# SECDONGL_001.net
KiCad netlist of a schematic drawn in EAGLE
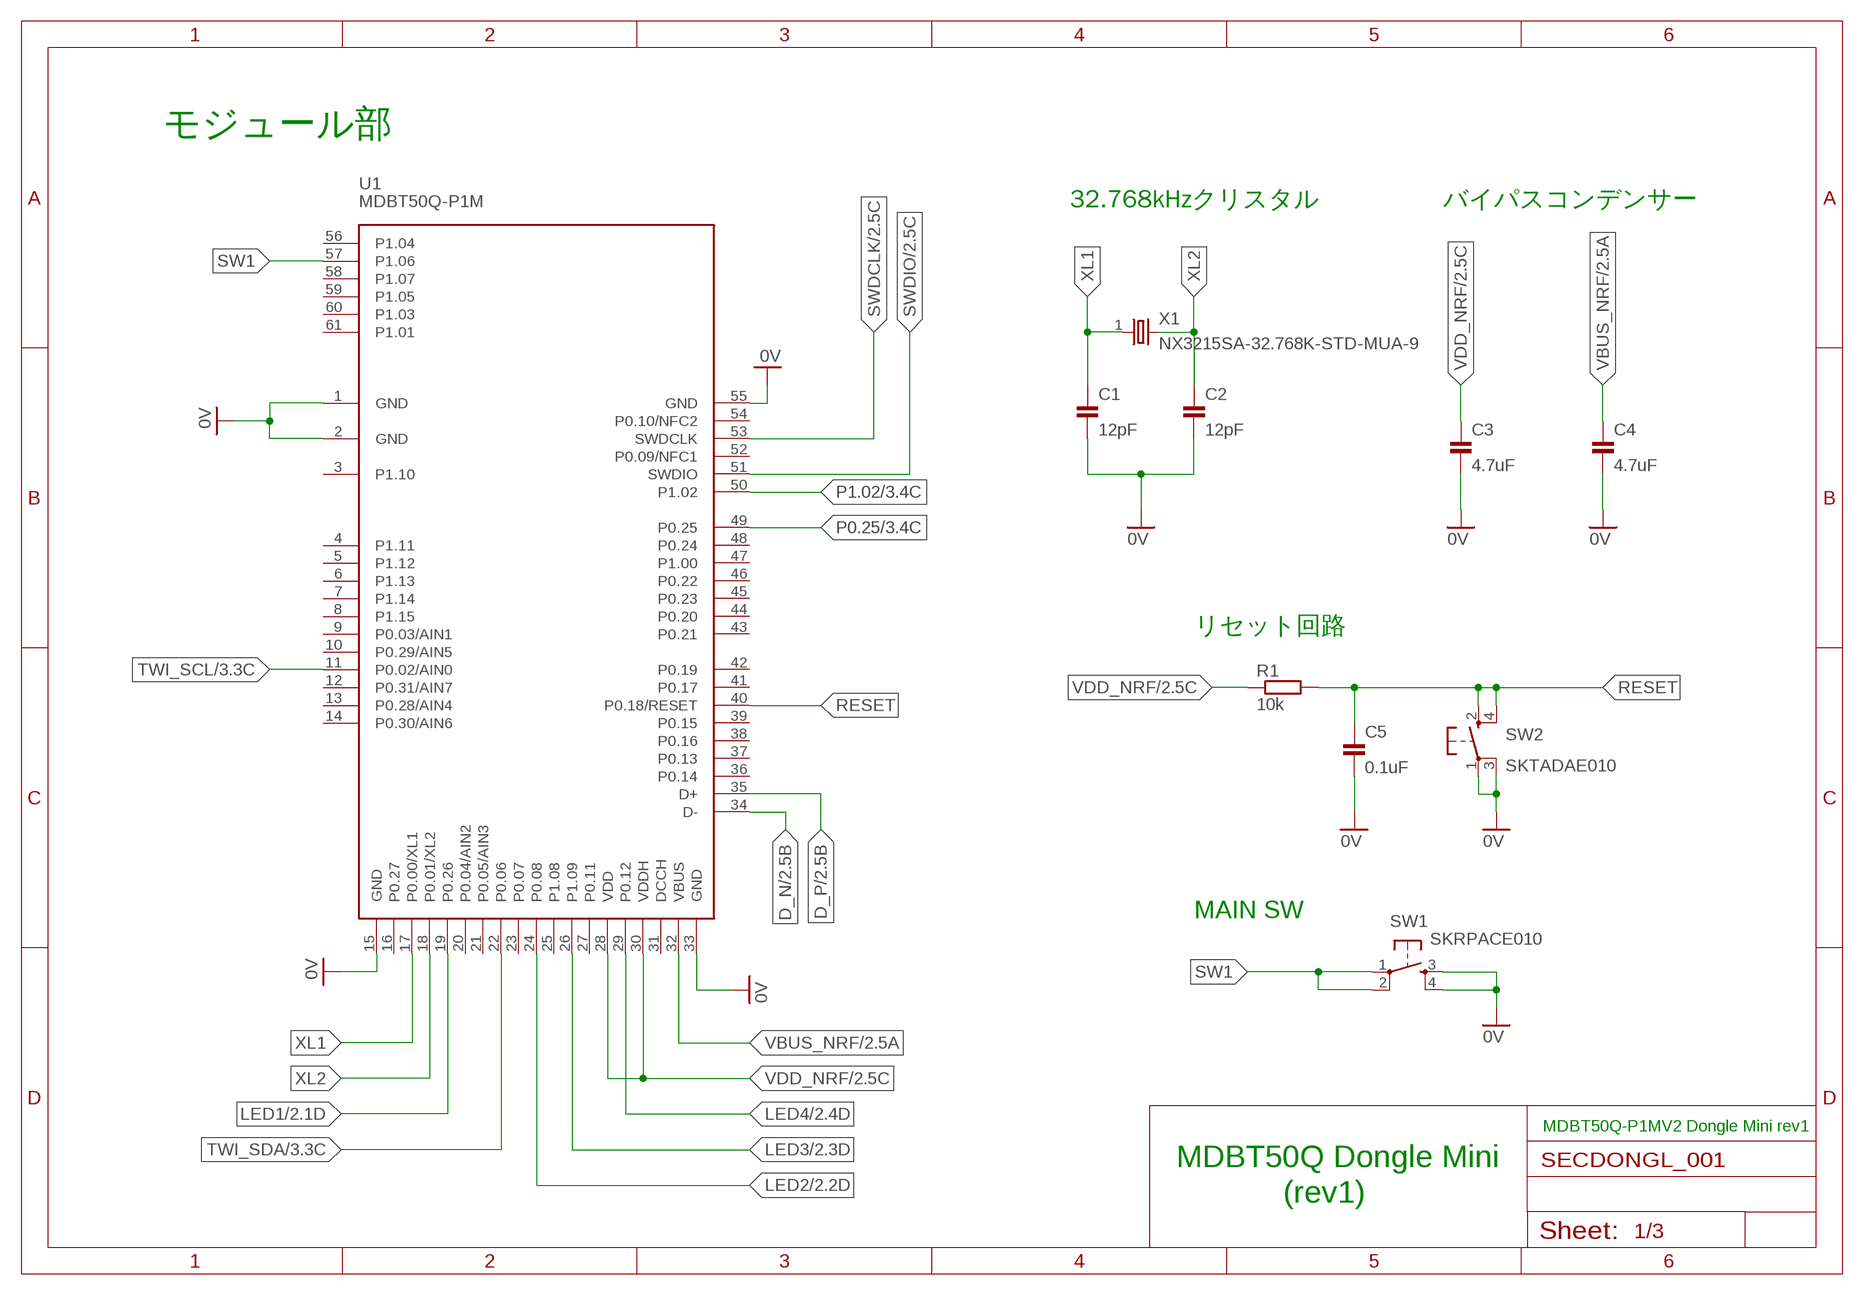
[diagram p0: schematic, sheet 1]
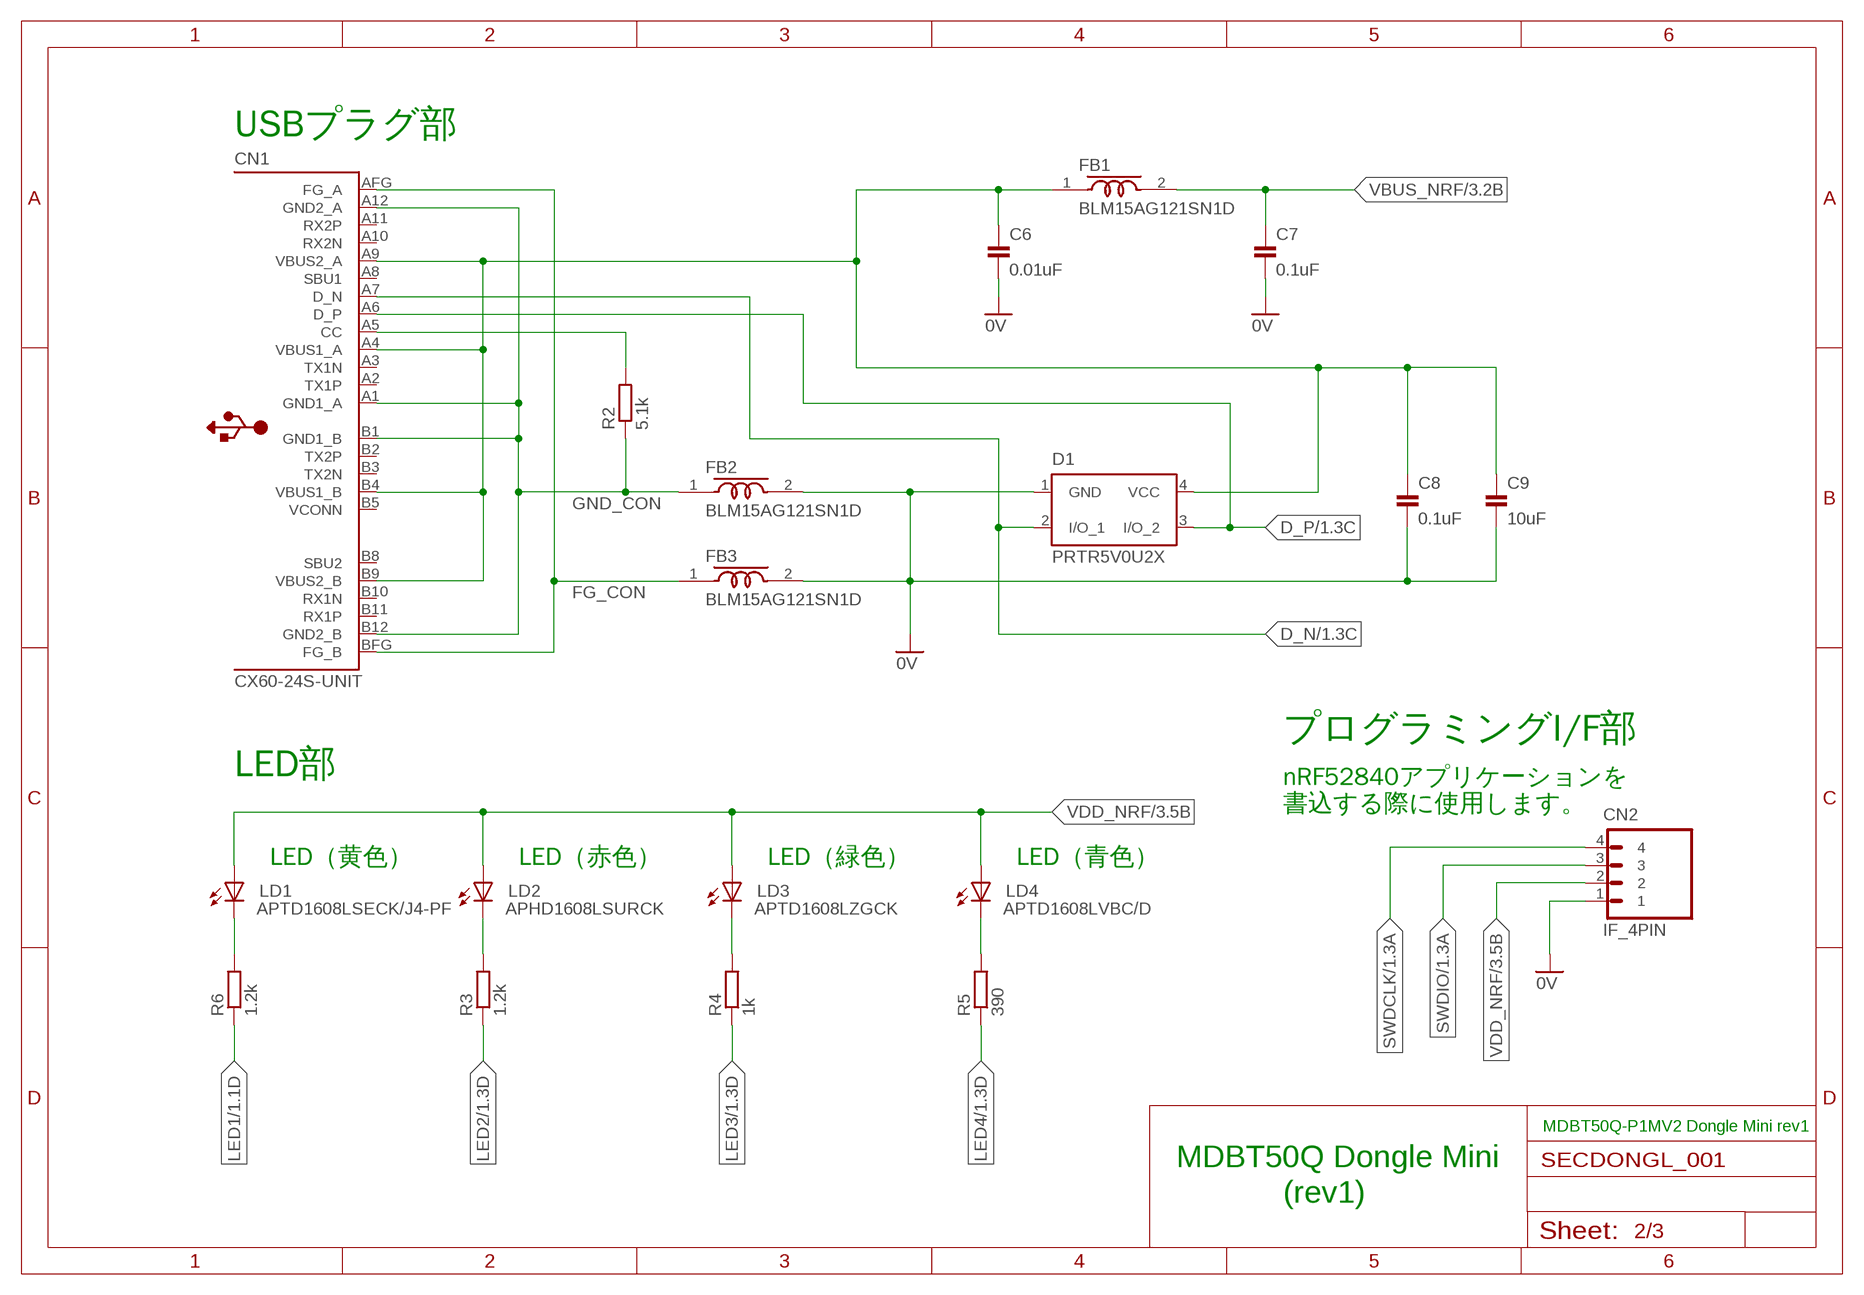
[diagram p1: schematic, sheet 2]
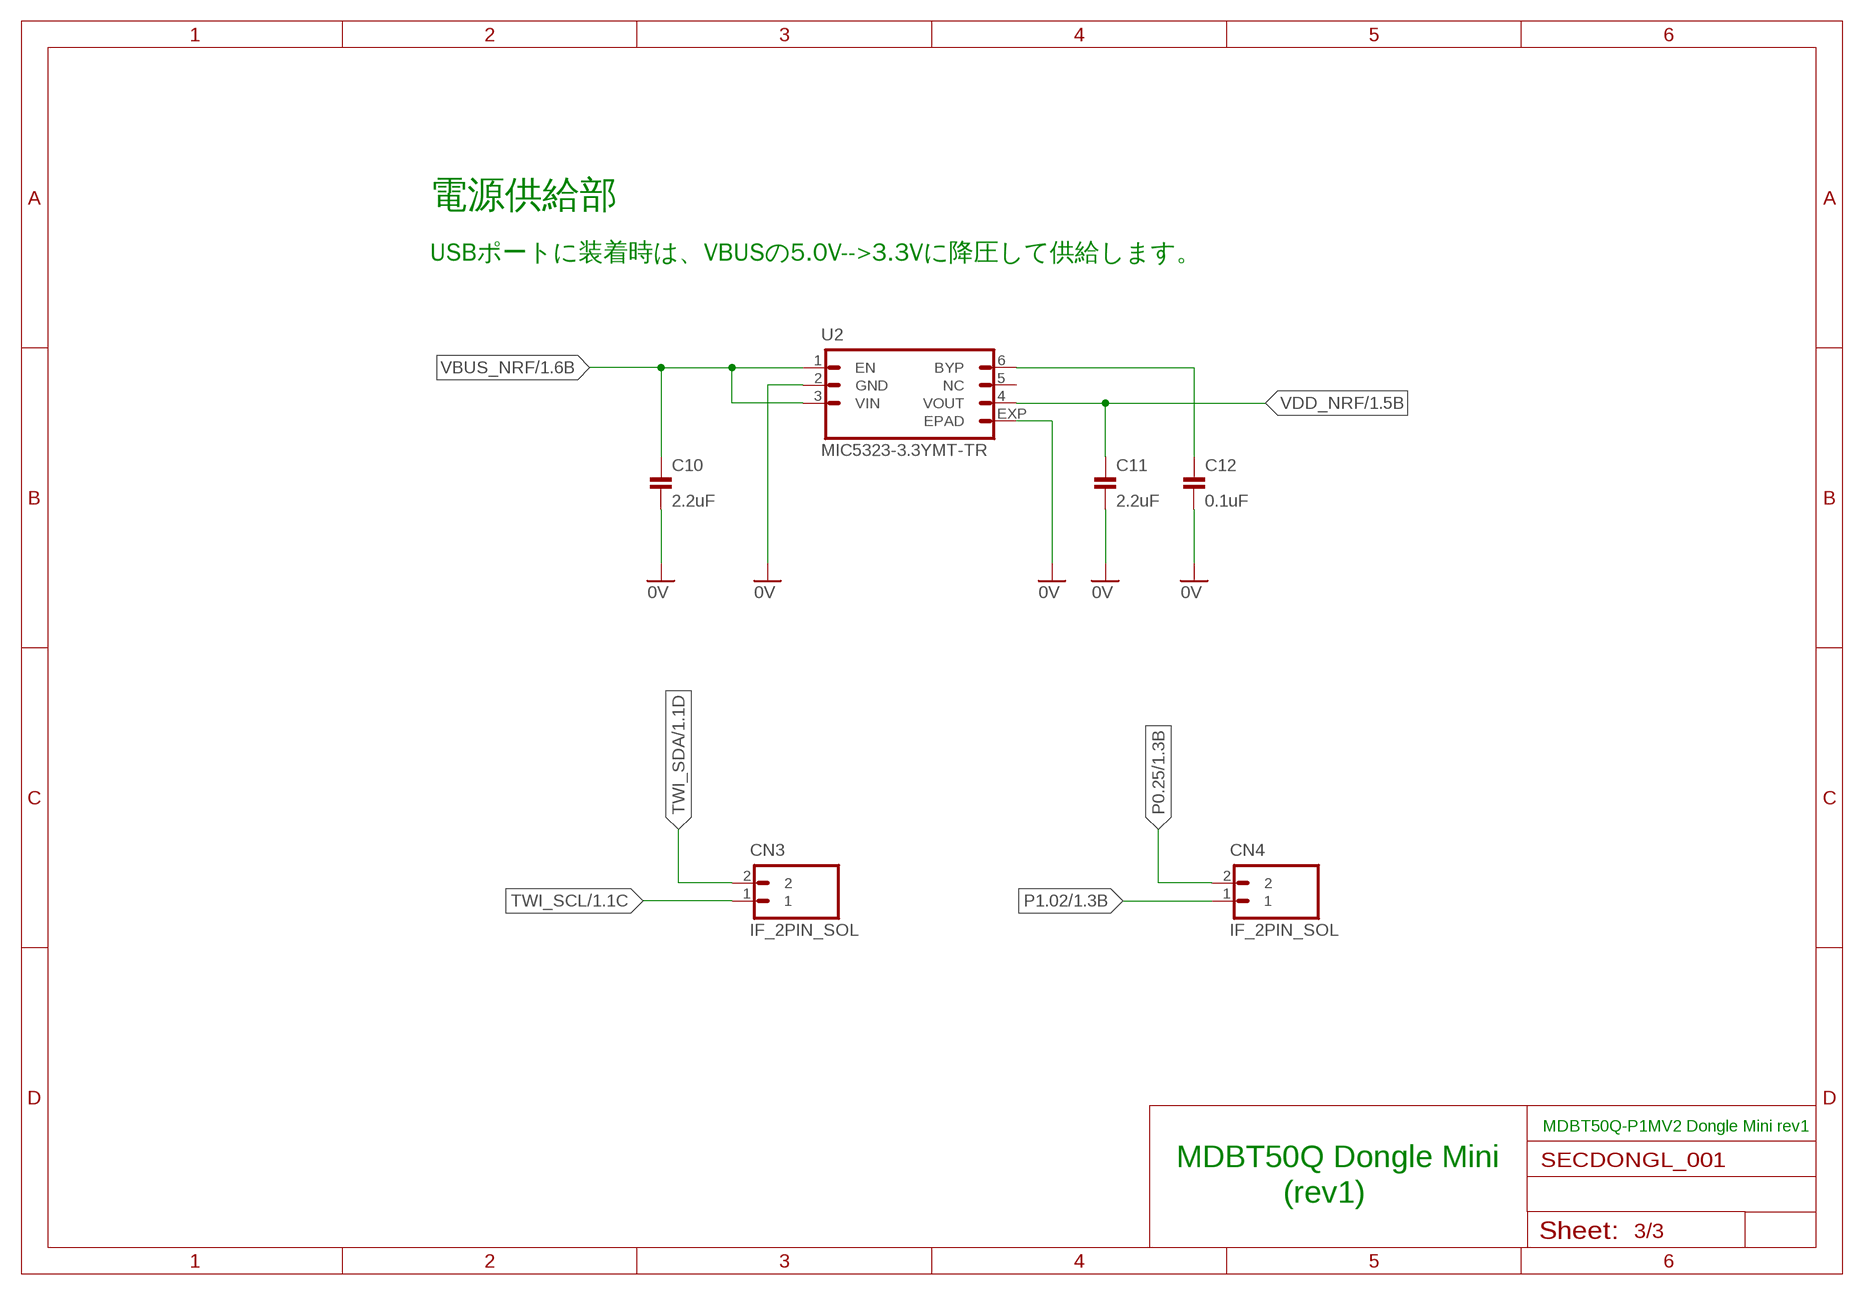
[diagram p2: schematic, sheet 3]

(export (version "E")
  (design (tool "Eeschema 10.0.6"))
  (components
    (comp (ref "C6")
      (value "0.01uF")
      (footprint "eagle-import:C0402K")
      (libsource (lib "eagle-import") (part "CAP_0402K"))
    )
    (comp (ref "C7")
      (value "0.1uF")
      (footprint "eagle-import:C0402K")
      (libsource (lib "eagle-import") (part "CAP_0402K"))
    )
    (comp (ref "C8")
      (value "0.1uF")
      (footprint "eagle-import:C0402K")
      (libsource (lib "eagle-import") (part "CAP_0402K"))
    )
    (comp (ref "C9")
      (value "10uF")
      (footprint "eagle-import:C0603K")
      (libsource (lib "eagle-import") (part "CAP_0603"))
    )
    (comp (ref "CN1")
      (value "CX60-24S-UNIT")
      (footprint "eagle-import:CX60-24S-UNIT")
      (libsource (lib "eagle-import") (part "CX60-24S-UNIT"))
    )
    (comp (ref "CN2")
      (value "IF_4PIN")
      (footprint "eagle-import:HEADER_4PIN")
      (libsource (lib "eagle-import") (part "IF_4PIN"))
    )
    (comp (ref "D1")
      (value "PRTR5V0U2X")
      (footprint "eagle-import:SOT143B")
      (libsource (lib "eagle-import") (part "PRTR5V0U2X"))
    )
    (comp (ref "FB1")
      (value "BLM15AG121SN1D")
      (footprint "eagle-import:C0402K")
      (libsource (lib "eagle-import") (part "BLM15AG121SN1D"))
    )
    (comp (ref "FB2")
      (value "BLM15AG121SN1D")
      (footprint "eagle-import:C0402K")
      (libsource (lib "eagle-import") (part "BLM15AG121SN1D"))
    )
    (comp (ref "FB3")
      (value "BLM15AG121SN1D")
      (footprint "eagle-import:C0402K")
      (libsource (lib "eagle-import") (part "BLM15AG121SN1D"))
    )
    (comp (ref "LD1")
      (value "APTD1608LSECK/J4-PF")
      (footprint "eagle-import:APTD1608")
      (libsource (lib "eagle-import") (part "APTD1608LSECK/J4-PF"))
    )
    (comp (ref "LD2")
      (value "APHD1608LSURCK")
      (footprint "eagle-import:APTD1608")
      (libsource (lib "eagle-import") (part "APHD1608LSURCK"))
    )
    (comp (ref "LD3")
      (value "APTD1608LZGCK")
      (footprint "eagle-import:APTD1608")
      (libsource (lib "eagle-import") (part "APTD1608LZGCK"))
    )
    (comp (ref "LD4")
      (value "APTD1608LVBC/D")
      (footprint "eagle-import:APTD1608")
      (libsource (lib "eagle-import") (part "APTD1608LVBC/D"))
    )
    (comp (ref "R2")
      (value "5.1k")
      (footprint "eagle-import:R0402")
      (libsource (lib "eagle-import") (part "RESISTOR_0402"))
    )
    (comp (ref "R3")
      (value "1.2k")
      (footprint "eagle-import:R0402")
      (libsource (lib "eagle-import") (part "RESISTOR_0402"))
    )
    (comp (ref "R4")
      (value "1k")
      (footprint "eagle-import:R0402")
      (libsource (lib "eagle-import") (part "RESISTOR_0402"))
    )
    (comp (ref "R5")
      (value "390")
      (footprint "eagle-import:R0402")
      (libsource (lib "eagle-import") (part "RESISTOR_0402"))
    )
    (comp (ref "R6")
      (value "1.2k")
      (footprint "eagle-import:R0402")
      (libsource (lib "eagle-import") (part "RESISTOR_0402"))
    )
    (comp (ref "C1")
      (value "12pF")
      (footprint "eagle-import:C0603K")
      (libsource (lib "eagle-import") (part "CAP_0603"))
    )
    (comp (ref "C2")
      (value "12pF")
      (footprint "eagle-import:C0603K")
      (libsource (lib "eagle-import") (part "CAP_0603"))
    )
    (comp (ref "C3")
      (value "4.7uF")
      (footprint "eagle-import:C0603K")
      (libsource (lib "eagle-import") (part "CAP_0603"))
    )
    (comp (ref "C4")
      (value "4.7uF")
      (footprint "eagle-import:C0603K")
      (libsource (lib "eagle-import") (part "CAP_0603"))
    )
    (comp (ref "C5")
      (value "0.1uF")
      (footprint "eagle-import:C0402K")
      (libsource (lib "eagle-import") (part "CAP_0402K"))
    )
    (comp (ref "R1")
      (value "10k")
      (footprint "eagle-import:R0402")
      (libsource (lib "eagle-import") (part "RESISTOR_0402"))
    )
    (comp (ref "SW1")
      (value "SKRPACE010")
      (footprint "eagle-import:SKRPACE010")
      (libsource (lib "eagle-import") (part "SKRPACE010"))
    )
    (comp (ref "SW2")
      (value "SKTADAE010")
      (footprint "eagle-import:SKTADAE010")
      (libsource (lib "eagle-import") (part "SKTADAE010"))
    )
    (comp (ref "U1")
      (value "MDBT50Q-P1M")
      (footprint "eagle-import:MDBT50Q-P1M")
      (libsource (lib "eagle-import") (part "MDBT50Q-P1M"))
    )
    (comp (ref "X1")
      (value "NX3215SA-32.768K-STD-MUA-9")
      (footprint "eagle-import:NX3215")
      (libsource (lib "eagle-import") (part "NX3215SA-32.768K-STD-MUA-9"))
    )
    (comp (ref "C10")
      (value "2.2uF")
      (footprint "eagle-import:C0603K")
      (libsource (lib "eagle-import") (part "CAP_0603"))
    )
    (comp (ref "C11")
      (value "2.2uF")
      (footprint "eagle-import:C0603K")
      (libsource (lib "eagle-import") (part "CAP_0603"))
    )
    (comp (ref "C12")
      (value "0.1uF")
      (footprint "eagle-import:C0402K")
      (libsource (lib "eagle-import") (part "CAP_0402K"))
    )
    (comp (ref "CN3")
      (value "IF_2PIN_SOL")
      (footprint "eagle-import:SOLPAD_2PIN")
      (libsource (lib "eagle-import") (part "IF_2PIN_SOL"))
    )
    (comp (ref "CN4")
      (value "IF_2PIN_SOL")
      (footprint "eagle-import:SOLPAD_2PIN")
      (libsource (lib "eagle-import") (part "IF_2PIN_SOL"))
    )
    (comp (ref "U2")
      (value "MIC5323-3.3YMT-TR")
      (footprint "eagle-import:6-VDFN(2X2)")
      (libsource (lib "eagle-import") (part "MIC5323-3.3YMT-TR"))
    )
  )
  (nets
    (net (code "1") (name "0V") (class "Default")
      (node (ref "C1") (pin "2") (pinfunction "2_2") (pintype "passive"))
      (node (ref "C10") (pin "2") (pinfunction "2_2") (pintype "passive"))
      (node (ref "C11") (pin "2") (pinfunction "2_2") (pintype "passive"))
      (node (ref "C12") (pin "2") (pinfunction "2_2") (pintype "passive"))
      (node (ref "C2") (pin "2") (pinfunction "2_2") (pintype "passive"))
      (node (ref "C3") (pin "2") (pinfunction "2_2") (pintype "passive"))
      (node (ref "C4") (pin "2") (pinfunction "2_2") (pintype "passive"))
      (node (ref "C5") (pin "2") (pinfunction "2_2") (pintype "passive"))
      (node (ref "C6") (pin "2") (pinfunction "2_2") (pintype "passive"))
      (node (ref "C7") (pin "2") (pinfunction "2_2") (pintype "passive"))
      (node (ref "C8") (pin "2") (pinfunction "2_2") (pintype "passive"))
      (node (ref "C9") (pin "2") (pinfunction "2_2") (pintype "passive"))
      (node (ref "CN2") (pin "1") (pinfunction "1_1") (pintype "passive"))
      (node (ref "D1") (pin "1") (pinfunction "GND_1") (pintype "passive"))
      (node (ref "FB2") (pin "2") (pinfunction "2_2") (pintype "passive"))
      (node (ref "FB3") (pin "2") (pinfunction "2_2") (pintype "passive"))
      (node (ref "SW1") (pin "3") (pinfunction "S_3") (pintype "passive"))
      (node (ref "SW1") (pin "4") (pinfunction "S1_4") (pintype "passive"))
      (node (ref "SW2") (pin "1") (pinfunction "P_1") (pintype "passive"))
      (node (ref "SW2") (pin "3") (pinfunction "P1_3") (pintype "passive"))
      (node (ref "U1") (pin "1") (pinfunction "GND_1") (pintype "bidirectional"))
      (node (ref "U1") (pin "15") (pinfunction "GND_15") (pintype "bidirectional"))
      (node (ref "U1") (pin "2") (pinfunction "GND_2") (pintype "bidirectional"))
      (node (ref "U1") (pin "33") (pinfunction "GND_33") (pintype "bidirectional"))
      (node (ref "U1") (pin "55") (pinfunction "GND_55") (pintype "bidirectional"))
      (node (ref "U2") (pin "2") (pinfunction "GND_2") (pintype "passive"))
      (node (ref "U2") (pin "EXP") (pinfunction "EPAD_EXP") (pintype "passive"))
    )
    (net (code "2") (name "D_N") (class "Default")
      (node (ref "CN1") (pin "A7") (pinfunction "D_N_A7") (pintype "bidirectional"))
      (node (ref "D1") (pin "2") (pinfunction "I/O_1_2") (pintype "bidirectional"))
      (node (ref "U1") (pin "34") (pinfunction "D-_34") (pintype "bidirectional"))
    )
    (net (code "3") (name "D_P") (class "Default")
      (node (ref "CN1") (pin "A6") (pinfunction "D_P_A6") (pintype "bidirectional"))
      (node (ref "D1") (pin "3") (pinfunction "I/O_2_3") (pintype "bidirectional"))
      (node (ref "U1") (pin "35") (pinfunction "D+_35") (pintype "bidirectional"))
    )
    (net (code "4") (name "FG_CON") (class "Default")
      (node (ref "CN1") (pin "AFG") (pinfunction "FG_A_AFG") (pintype "passive"))
      (node (ref "CN1") (pin "BFG") (pinfunction "FG_B_BFG") (pintype "passive"))
      (node (ref "FB3") (pin "1") (pinfunction "1_1") (pintype "passive"))
    )
    (net (code "5") (name "GND_CON") (class "Default")
      (node (ref "CN1") (pin "A1") (pinfunction "GND1_A_A1") (pintype "passive"))
      (node (ref "CN1") (pin "A12") (pinfunction "GND2_A_A12") (pintype "bidirectional"))
      (node (ref "CN1") (pin "B1") (pinfunction "GND1_B_B1") (pintype "passive"))
      (node (ref "CN1") (pin "B12") (pinfunction "GND2_B_B12") (pintype "passive"))
      (node (ref "FB2") (pin "1") (pinfunction "1_1") (pintype "passive"))
      (node (ref "R2") (pin "1") (pinfunction "1_1") (pintype "passive"))
    )
    (net (code "6") (name "LED1") (class "Default")
      (node (ref "R6") (pin "1") (pinfunction "1_1") (pintype "passive"))
      (node (ref "U1") (pin "19") (pinfunction "P0.26_19") (pintype "bidirectional"))
    )
    (net (code "7") (name "LED2") (class "Default")
      (node (ref "R3") (pin "1") (pinfunction "1_1") (pintype "passive"))
      (node (ref "U1") (pin "24") (pinfunction "P0.08_24") (pintype "bidirectional"))
    )
    (net (code "8") (name "LED3") (class "Default")
      (node (ref "R4") (pin "1") (pinfunction "1_1") (pintype "passive"))
      (node (ref "U1") (pin "26") (pinfunction "P1.09_26") (pintype "bidirectional"))
    )
    (net (code "9") (name "LED4") (class "Default")
      (node (ref "R5") (pin "1") (pinfunction "1_1") (pintype "passive"))
      (node (ref "U1") (pin "29") (pinfunction "P0.12_29") (pintype "bidirectional"))
    )
    (net (code "10") (name "Net-(CN1-CC)") (class "Default")
      (node (ref "CN1") (pin "A5") (pinfunction "CC_A5") (pintype "passive"))
      (node (ref "R2") (pin "2") (pinfunction "2_2") (pintype "passive"))
    )
    (net (code "11") (name "Net-(CN1-VBUS1_A)") (class "Default")
      (node (ref "C6") (pin "1") (pinfunction "1_1") (pintype "passive"))
      (node (ref "C8") (pin "1") (pinfunction "1_1") (pintype "passive"))
      (node (ref "C9") (pin "1") (pinfunction "1_1") (pintype "passive"))
      (node (ref "CN1") (pin "A4") (pinfunction "VBUS1_A_A4") (pintype "passive"))
      (node (ref "CN1") (pin "A9") (pinfunction "VBUS2_A_A9") (pintype "passive"))
      (node (ref "CN1") (pin "B4") (pinfunction "VBUS1_B_B4") (pintype "passive"))
      (node (ref "CN1") (pin "B9") (pinfunction "VBUS2_B_B9") (pintype "passive"))
      (node (ref "D1") (pin "4") (pinfunction "VCC_4") (pintype "passive"))
      (node (ref "FB1") (pin "1") (pinfunction "1_1") (pintype "passive"))
    )
    (net (code "12") (name "Net-(LD1-PadC)") (class "Default")
      (node (ref "LD1") (pin "C") (pinfunction "C_C") (pintype "passive"))
      (node (ref "R6") (pin "2") (pinfunction "2_2") (pintype "passive"))
    )
    (net (code "13") (name "Net-(LD2-PadC)") (class "Default")
      (node (ref "LD2") (pin "C") (pinfunction "C_C") (pintype "passive"))
      (node (ref "R3") (pin "2") (pinfunction "2_2") (pintype "passive"))
    )
    (net (code "14") (name "Net-(LD3-PadC)") (class "Default")
      (node (ref "LD3") (pin "C") (pinfunction "C_C") (pintype "passive"))
      (node (ref "R4") (pin "2") (pinfunction "2_2") (pintype "passive"))
    )
    (net (code "15") (name "Net-(LD4-PadC)") (class "Default")
      (node (ref "LD4") (pin "C") (pinfunction "C_C") (pintype "passive"))
      (node (ref "R5") (pin "2") (pinfunction "2_2") (pintype "passive"))
    )
    (net (code "16") (name "Net-(U2-BYP)") (class "Default")
      (node (ref "C12") (pin "1") (pinfunction "1_1") (pintype "passive"))
      (node (ref "U2") (pin "6") (pinfunction "BYP_6") (pintype "passive"))
    )
    (net (code "17") (name "P0.25") (class "Default")
      (node (ref "CN4") (pin "2") (pinfunction "2_2") (pintype "passive"))
      (node (ref "U1") (pin "49") (pinfunction "P0.25_49") (pintype "bidirectional"))
    )
    (net (code "18") (name "P1.02") (class "Default")
      (node (ref "CN4") (pin "1") (pinfunction "1_1") (pintype "passive"))
      (node (ref "U1") (pin "50") (pinfunction "P1.02_50") (pintype "bidirectional"))
    )
    (net (code "19") (name "RESET") (class "Default")
      (node (ref "C5") (pin "1") (pinfunction "1_1") (pintype "passive"))
      (node (ref "R1") (pin "2") (pinfunction "2_2") (pintype "passive"))
      (node (ref "SW2") (pin "2") (pinfunction "S_2") (pintype "passive"))
      (node (ref "SW2") (pin "4") (pinfunction "S1_4") (pintype "passive"))
      (node (ref "U1") (pin "40") (pinfunction "P0.18/RESET_40") (pintype "bidirectional"))
    )
    (net (code "20") (name "SW1") (class "Default")
      (node (ref "SW1") (pin "1") (pinfunction "P_1") (pintype "passive"))
      (node (ref "SW1") (pin "2") (pinfunction "P1_2") (pintype "passive"))
      (node (ref "U1") (pin "57") (pinfunction "P1.06_57") (pintype "bidirectional"))
    )
    (net (code "21") (name "SWDCLK") (class "Default")
      (node (ref "CN2") (pin "4") (pinfunction "4_4") (pintype "passive"))
      (node (ref "U1") (pin "53") (pinfunction "SWDCLK_53") (pintype "bidirectional"))
    )
    (net (code "22") (name "SWDIO") (class "Default")
      (node (ref "CN2") (pin "3") (pinfunction "3_3") (pintype "passive"))
      (node (ref "U1") (pin "51") (pinfunction "SWDIO_51") (pintype "bidirectional"))
    )
    (net (code "23") (name "TWI_SCL") (class "Default")
      (node (ref "CN3") (pin "1") (pinfunction "1_1") (pintype "passive"))
      (node (ref "U1") (pin "11") (pinfunction "P0.02/AIN0_11") (pintype "bidirectional"))
    )
    (net (code "24") (name "TWI_SDA") (class "Default")
      (node (ref "CN3") (pin "2") (pinfunction "2_2") (pintype "passive"))
      (node (ref "U1") (pin "22") (pinfunction "P0.06_22") (pintype "bidirectional"))
    )
    (net (code "25") (name "VBUS_NRF") (class "Default")
      (node (ref "C10") (pin "1") (pinfunction "1_1") (pintype "passive"))
      (node (ref "C4") (pin "1") (pinfunction "1_1") (pintype "passive"))
      (node (ref "C7") (pin "1") (pinfunction "1_1") (pintype "passive"))
      (node (ref "FB1") (pin "2") (pinfunction "2_2") (pintype "passive"))
      (node (ref "U1") (pin "32") (pinfunction "VBUS_32") (pintype "bidirectional"))
      (node (ref "U2") (pin "1") (pinfunction "EN_1") (pintype "bidirectional"))
      (node (ref "U2") (pin "3") (pinfunction "VIN_3") (pintype "passive"))
    )
    (net (code "26") (name "VDD_NRF") (class "Default")
      (node (ref "C11") (pin "1") (pinfunction "1_1") (pintype "passive"))
      (node (ref "C3") (pin "1") (pinfunction "1_1") (pintype "passive"))
      (node (ref "CN2") (pin "2") (pinfunction "2_2") (pintype "passive"))
      (node (ref "LD1") (pin "A") (pinfunction "A_A") (pintype "passive"))
      (node (ref "LD2") (pin "A") (pinfunction "A_A") (pintype "passive"))
      (node (ref "LD3") (pin "A") (pinfunction "A_A") (pintype "passive"))
      (node (ref "LD4") (pin "A") (pinfunction "A_A") (pintype "passive"))
      (node (ref "R1") (pin "1") (pinfunction "1_1") (pintype "passive"))
      (node (ref "U1") (pin "28") (pinfunction "VDD_28") (pintype "bidirectional"))
      (node (ref "U1") (pin "30") (pinfunction "VDDH_30") (pintype "bidirectional"))
      (node (ref "U2") (pin "4") (pinfunction "VOUT_4") (pintype "passive"))
    )
    (net (code "27") (name "XL1") (class "Default")
      (node (ref "C1") (pin "1") (pinfunction "1_1") (pintype "passive"))
      (node (ref "U1") (pin "17") (pinfunction "P0.00/XL1_17") (pintype "bidirectional"))
      (node (ref "X1") (pin "1") (pinfunction "1_1") (pintype "passive"))
    )
    (net (code "28") (name "XL2") (class "Default")
      (node (ref "C2") (pin "1") (pinfunction "1_1") (pintype "passive"))
      (node (ref "U1") (pin "18") (pinfunction "P0.01/XL2_18") (pintype "bidirectional"))
      (node (ref "X1") (pin "2") (pinfunction "2_2") (pintype "passive"))
    )
    (net (code "29") (name "unconnected-(CN1-RX1N-PadB10)") (class "Default")
      (node (ref "CN1") (pin "B10") (pinfunction "RX1N_B10") (pintype "bidirectional"))
    )
    (net (code "30") (name "unconnected-(CN1-RX1P-PadB11)") (class "Default")
      (node (ref "CN1") (pin "B11") (pinfunction "RX1P_B11") (pintype "bidirectional"))
    )
    (net (code "31") (name "unconnected-(CN1-RX2N-PadA10)") (class "Default")
      (node (ref "CN1") (pin "A10") (pinfunction "RX2N_A10") (pintype "passive"))
    )
    (net (code "32") (name "unconnected-(CN1-RX2P-PadA11)") (class "Default")
      (node (ref "CN1") (pin "A11") (pinfunction "RX2P_A11") (pintype "bidirectional"))
    )
    (net (code "33") (name "unconnected-(CN1-SBU1-PadA8)") (class "Default")
      (node (ref "CN1") (pin "A8") (pinfunction "SBU1_A8") (pintype "passive"))
    )
    (net (code "34") (name "unconnected-(CN1-SBU2-PadB8)") (class "Default")
      (node (ref "CN1") (pin "B8") (pinfunction "SBU2_B8") (pintype "passive"))
    )
    (net (code "35") (name "unconnected-(CN1-TX1N-PadA3)") (class "Default")
      (node (ref "CN1") (pin "A3") (pinfunction "TX1N_A3") (pintype "bidirectional"))
    )
    (net (code "36") (name "unconnected-(CN1-TX1P-PadA2)") (class "Default")
      (node (ref "CN1") (pin "A2") (pinfunction "TX1P_A2") (pintype "bidirectional"))
    )
    (net (code "37") (name "unconnected-(CN1-TX2N-PadB3)") (class "Default")
      (node (ref "CN1") (pin "B3") (pinfunction "TX2N_B3") (pintype "bidirectional"))
    )
    (net (code "38") (name "unconnected-(CN1-TX2P-PadB2)") (class "Default")
      (node (ref "CN1") (pin "B2") (pinfunction "TX2P_B2") (pintype "bidirectional"))
    )
    (net (code "39") (name "unconnected-(CN1-VCONN-PadB5)") (class "Default")
      (node (ref "CN1") (pin "B5") (pinfunction "VCONN_B5") (pintype "passive"))
    )
    (net (code "40") (name "unconnected-(U1-DCCH-Pad31)") (class "Default")
      (node (ref "U1") (pin "31") (pinfunction "DCCH_31") (pintype "bidirectional"))
    )
    (net (code "41") (name "unconnected-(U1-P0.03{slash}AIN1-Pad9)") (class "Default")
      (node (ref "U1") (pin "9") (pinfunction "P0.03/AIN1_9") (pintype "bidirectional"))
    )
    (net (code "42") (name "unconnected-(U1-P0.04{slash}AIN2-Pad20)") (class "Default")
      (node (ref "U1") (pin "20") (pinfunction "P0.04/AIN2_20") (pintype "bidirectional"))
    )
    (net (code "43") (name "unconnected-(U1-P0.05{slash}AIN3-Pad21)") (class "Default")
      (node (ref "U1") (pin "21") (pinfunction "P0.05/AIN3_21") (pintype "bidirectional"))
    )
    (net (code "44") (name "unconnected-(U1-P0.07-Pad23)") (class "Default")
      (node (ref "U1") (pin "23") (pinfunction "P0.07_23") (pintype "bidirectional"))
    )
    (net (code "45") (name "unconnected-(U1-P0.09{slash}NFC1-Pad52)") (class "Default")
      (node (ref "U1") (pin "52") (pinfunction "P0.09/NFC1_52") (pintype "bidirectional"))
    )
    (net (code "46") (name "unconnected-(U1-P0.10{slash}NFC2-Pad54)") (class "Default")
      (node (ref "U1") (pin "54") (pinfunction "P0.10/NFC2_54") (pintype "bidirectional"))
    )
    (net (code "47") (name "unconnected-(U1-P0.11-Pad27)") (class "Default")
      (node (ref "U1") (pin "27") (pinfunction "P0.11_27") (pintype "bidirectional"))
    )
    (net (code "48") (name "unconnected-(U1-P0.13-Pad37)") (class "Default")
      (node (ref "U1") (pin "37") (pinfunction "P0.13_37") (pintype "bidirectional"))
    )
    (net (code "49") (name "unconnected-(U1-P0.14-Pad36)") (class "Default")
      (node (ref "U1") (pin "36") (pinfunction "P0.14_36") (pintype "bidirectional"))
    )
    (net (code "50") (name "unconnected-(U1-P0.15-Pad39)") (class "Default")
      (node (ref "U1") (pin "39") (pinfunction "P0.15_39") (pintype "bidirectional"))
    )
    (net (code "51") (name "unconnected-(U1-P0.16-Pad38)") (class "Default")
      (node (ref "U1") (pin "38") (pinfunction "P0.16_38") (pintype "bidirectional"))
    )
    (net (code "52") (name "unconnected-(U1-P0.17-Pad41)") (class "Default")
      (node (ref "U1") (pin "41") (pinfunction "P0.17_41") (pintype "bidirectional"))
    )
    (net (code "53") (name "unconnected-(U1-P0.19-Pad42)") (class "Default")
      (node (ref "U1") (pin "42") (pinfunction "P0.19_42") (pintype "bidirectional"))
    )
    (net (code "54") (name "unconnected-(U1-P0.20-Pad44)") (class "Default")
      (node (ref "U1") (pin "44") (pinfunction "P0.20_44") (pintype "bidirectional"))
    )
    (net (code "55") (name "unconnected-(U1-P0.21-Pad43)") (class "Default")
      (node (ref "U1") (pin "43") (pinfunction "P0.21_43") (pintype "bidirectional"))
    )
    (net (code "56") (name "unconnected-(U1-P0.22-Pad46)") (class "Default")
      (node (ref "U1") (pin "46") (pinfunction "P0.22_46") (pintype "bidirectional"))
    )
    (net (code "57") (name "unconnected-(U1-P0.23-Pad45)") (class "Default")
      (node (ref "U1") (pin "45") (pinfunction "P0.23_45") (pintype "bidirectional"))
    )
    (net (code "58") (name "unconnected-(U1-P0.24-Pad48)") (class "Default")
      (node (ref "U1") (pin "48") (pinfunction "P0.24_48") (pintype "bidirectional"))
    )
    (net (code "59") (name "unconnected-(U1-P0.27-Pad16)") (class "Default")
      (node (ref "U1") (pin "16") (pinfunction "P0.27_16") (pintype "bidirectional"))
    )
    (net (code "60") (name "unconnected-(U1-P0.28{slash}AIN4-Pad13)") (class "Default")
      (node (ref "U1") (pin "13") (pinfunction "P0.28/AIN4_13") (pintype "bidirectional"))
    )
    (net (code "61") (name "unconnected-(U1-P0.29{slash}AIN5-Pad10)") (class "Default")
      (node (ref "U1") (pin "10") (pinfunction "P0.29/AIN5_10") (pintype "bidirectional"))
    )
    (net (code "62") (name "unconnected-(U1-P0.30{slash}AIN6-Pad14)") (class "Default")
      (node (ref "U1") (pin "14") (pinfunction "P0.30/AIN6_14") (pintype "bidirectional"))
    )
    (net (code "63") (name "unconnected-(U1-P0.31{slash}AIN7-Pad12)") (class "Default")
      (node (ref "U1") (pin "12") (pinfunction "P0.31/AIN7_12") (pintype "bidirectional"))
    )
    (net (code "64") (name "unconnected-(U1-P1.00-Pad47)") (class "Default")
      (node (ref "U1") (pin "47") (pinfunction "P1.00_47") (pintype "bidirectional"))
    )
    (net (code "65") (name "unconnected-(U1-P1.01-Pad61)") (class "Default")
      (node (ref "U1") (pin "61") (pinfunction "P1.01_61") (pintype "bidirectional"))
    )
    (net (code "66") (name "unconnected-(U1-P1.03-Pad60)") (class "Default")
      (node (ref "U1") (pin "60") (pinfunction "P1.03_60") (pintype "bidirectional"))
    )
    (net (code "67") (name "unconnected-(U1-P1.04-Pad56)") (class "Default")
      (node (ref "U1") (pin "56") (pinfunction "P1.04_56") (pintype "bidirectional"))
    )
    (net (code "68") (name "unconnected-(U1-P1.05-Pad59)") (class "Default")
      (node (ref "U1") (pin "59") (pinfunction "P1.05_59") (pintype "bidirectional"))
    )
    (net (code "69") (name "unconnected-(U1-P1.07-Pad58)") (class "Default")
      (node (ref "U1") (pin "58") (pinfunction "P1.07_58") (pintype "bidirectional"))
    )
    (net (code "70") (name "unconnected-(U1-P1.08-Pad25)") (class "Default")
      (node (ref "U1") (pin "25") (pinfunction "P1.08_25") (pintype "bidirectional"))
    )
    (net (code "71") (name "unconnected-(U1-P1.10-Pad3)") (class "Default")
      (node (ref "U1") (pin "3") (pinfunction "P1.10_3") (pintype "bidirectional"))
    )
    (net (code "72") (name "unconnected-(U1-P1.11-Pad4)") (class "Default")
      (node (ref "U1") (pin "4") (pinfunction "P1.11_4") (pintype "bidirectional"))
    )
    (net (code "73") (name "unconnected-(U1-P1.12-Pad5)") (class "Default")
      (node (ref "U1") (pin "5") (pinfunction "P1.12_5") (pintype "bidirectional"))
    )
    (net (code "74") (name "unconnected-(U1-P1.13-Pad6)") (class "Default")
      (node (ref "U1") (pin "6") (pinfunction "P1.13_6") (pintype "bidirectional"))
    )
    (net (code "75") (name "unconnected-(U1-P1.14-Pad7)") (class "Default")
      (node (ref "U1") (pin "7") (pinfunction "P1.14_7") (pintype "bidirectional"))
    )
    (net (code "76") (name "unconnected-(U1-P1.15-Pad8)") (class "Default")
      (node (ref "U1") (pin "8") (pinfunction "P1.15_8") (pintype "bidirectional"))
    )
    (net (code "77") (name "unconnected-(U2-NC-Pad5)") (class "Default")
      (node (ref "U2") (pin "5") (pinfunction "NC_5") (pintype "passive"))
    )
  )
)
